# uino-328th.net
KiCad netlist of a schematic drawn in EAGLE
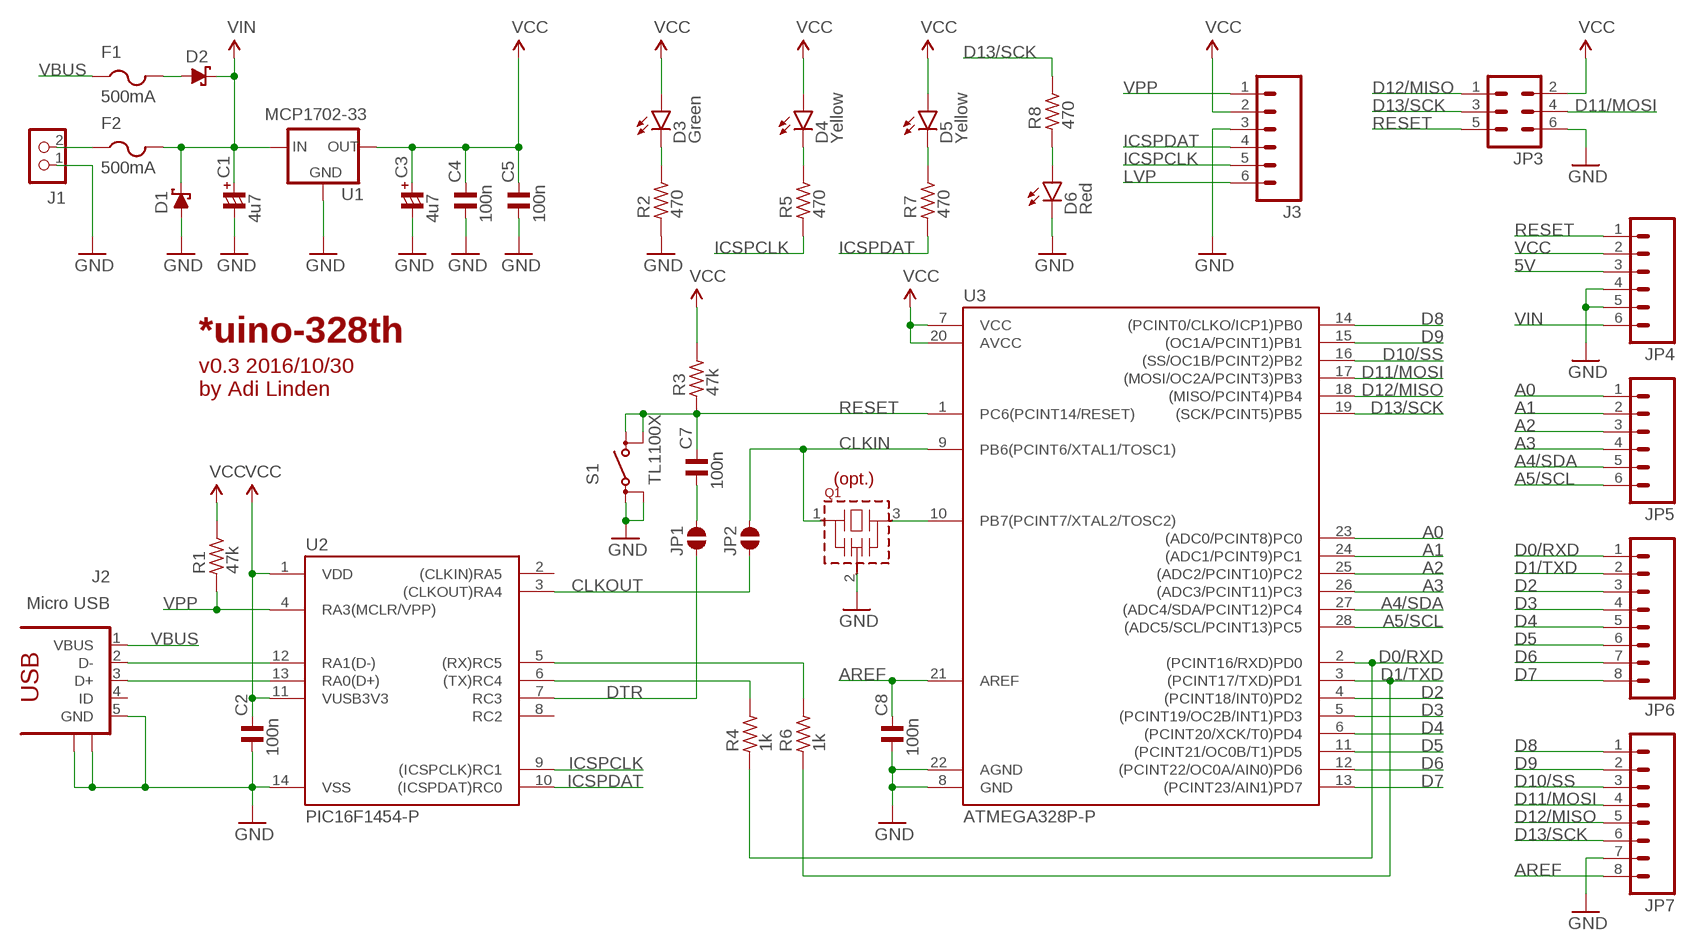
[diagram p0: schematic, sheet 1]

(export (version "E")
  (design (tool "Eeschema 10.0.6"))
  (components
    (comp (ref "C1")
      (value "4u7")
      (footprint "eagle-import:CTT-025-040")
      (libsource (lib "eagle-import") (part "CP_TT025-040"))
    )
    (comp (ref "C2")
      (value "100n")
      (footprint "eagle-import:C025-040X018")
      (libsource (lib "eagle-import") (part "C_C025-040X018"))
    )
    (comp (ref "C3")
      (value "4u7")
      (footprint "eagle-import:CTT-025-040")
      (libsource (lib "eagle-import") (part "CP_TT025-040"))
    )
    (comp (ref "C4")
      (value "100n")
      (footprint "eagle-import:C025-040X018")
      (libsource (lib "eagle-import") (part "C_C025-040X018"))
    )
    (comp (ref "C5")
      (value "100n")
      (footprint "eagle-import:C025-040X018")
      (libsource (lib "eagle-import") (part "C_C025-040X018"))
    )
    (comp (ref "C7")
      (value "100n")
      (footprint "eagle-import:C025-040X018")
      (libsource (lib "eagle-import") (part "C_C025-040X018"))
    )
    (comp (ref "C8")
      (value "100n")
      (footprint "eagle-import:C025-040X018")
      (libsource (lib "eagle-import") (part "C_C025-040X018"))
    )
    (comp (ref "D1")
      (value "SCHOTTKY-DIODEDO35-7")
      (footprint "eagle-import:DO35-7")
      (libsource (lib "eagle-import") (part "SCHOTTKY-DIODEDO35-7"))
    )
    (comp (ref "D2")
      (value "SCHOTTKY-DIODEDO35-7")
      (footprint "eagle-import:DO35-7")
      (libsource (lib "eagle-import") (part "SCHOTTKY-DIODEDO35-7"))
    )
    (comp (ref "D3")
      (value "Green")
      (footprint "eagle-import:LED3MM")
      (libsource (lib "eagle-import") (part "LED3MM"))
    )
    (comp (ref "D4")
      (value "Yellow")
      (footprint "eagle-import:LED3MM")
      (libsource (lib "eagle-import") (part "LED3MM"))
    )
    (comp (ref "D5")
      (value "Yellow")
      (footprint "eagle-import:LED3MM")
      (libsource (lib "eagle-import") (part "LED3MM"))
    )
    (comp (ref "D6")
      (value "Red")
      (footprint "eagle-import:LED3MM")
      (libsource (lib "eagle-import") (part "LED3MM"))
    )
    (comp (ref "F1")
      (value "500mA")
      (footprint "eagle-import:PTC")
      (libsource (lib "eagle-import") (part "FUSE_PTC-TH"))
    )
    (comp (ref "F2")
      (value "500mA")
      (footprint "eagle-import:PTC")
      (libsource (lib "eagle-import") (part "FUSE_PTC-TH"))
    )
    (comp (ref "J1")
      (value "CON_TERMINAL_BLOCK_02-5MM")
      (footprint "eagle-import:TERMINAL_BLOCK_2P_5")
      (libsource (lib "eagle-import") (part "CON_TERMINAL_BLOCK_02-5MM"))
    )
    (comp (ref "J2")
      (value "Micro USB")
      (footprint "eagle-import:ZX62D-AB-5P8")
      (libsource (lib "eagle-import") (part "USB_MICRO_B_2.0-TH"))
    )
    (comp (ref "J3")
      (value "M06LOCK")
      (footprint "eagle-import:1X06_LOCK")
      (libsource (lib "eagle-import") (part "SparkFun-Connectors_M06LOCK"))
    )
    (comp (ref "JP1")
      (value "SJ-035")
      (footprint "eagle-import:SJ-035")
      (libsource (lib "eagle-import") (part "SJ-035"))
    )
    (comp (ref "JP2")
      (value "SJ-035")
      (footprint "eagle-import:SJ-035")
      (libsource (lib "eagle-import") (part "SJ-035"))
    )
    (comp (ref "JP3")
      (value "M03X2")
      (footprint "eagle-import:2X03")
      (libsource (lib "eagle-import") (part "M03X2"))
    )
    (comp (ref "JP4")
      (value "M06SIP")
      (footprint "eagle-import:1X06")
      (libsource (lib "eagle-import") (part "M06SIP"))
    )
    (comp (ref "JP5")
      (value "M06SIP")
      (footprint "eagle-import:1X06")
      (libsource (lib "eagle-import") (part "M06SIP"))
    )
    (comp (ref "JP6")
      (value "M081X08")
      (footprint "eagle-import:1X08")
      (libsource (lib "eagle-import") (part "M081X08"))
    )
    (comp (ref "JP7")
      (value "M081X08")
      (footprint "eagle-import:1X08")
      (libsource (lib "eagle-import") (part "M081X08"))
    )
    (comp (ref "Q1")
      (value "CSTLS_X")
      (footprint "eagle-import:CSTLS_X")
      (libsource (lib "eagle-import") (part "CSTLS_X"))
    )
    (comp (ref "R1")
      (value "47k")
      (footprint "eagle-import:0207_7")
      (libsource (lib "eagle-import") (part "R_X0207/7"))
    )
    (comp (ref "R2")
      (value "470")
      (footprint "eagle-import:0207_7")
      (libsource (lib "eagle-import") (part "R_X0207/7"))
    )
    (comp (ref "R3")
      (value "47k")
      (footprint "eagle-import:0207_7")
      (libsource (lib "eagle-import") (part "R_X0207/7"))
    )
    (comp (ref "R4")
      (value "1k")
      (footprint "eagle-import:0207_10")
      (libsource (lib "eagle-import") (part "R_X0207/10"))
    )
    (comp (ref "R5")
      (value "470")
      (footprint "eagle-import:0207_7")
      (libsource (lib "eagle-import") (part "R_X0207/7"))
    )
    (comp (ref "R6")
      (value "1k")
      (footprint "eagle-import:0207_10")
      (libsource (lib "eagle-import") (part "R_X0207/10"))
    )
    (comp (ref "R7")
      (value "470")
      (footprint "eagle-import:0207_7")
      (libsource (lib "eagle-import") (part "R_X0207/7"))
    )
    (comp (ref "R8")
      (value "470")
      (footprint "eagle-import:0207_10")
      (libsource (lib "eagle-import") (part "R_X0207/10"))
    )
    (comp (ref "S1")
      (value "TL1100X")
      (footprint "eagle-import:TL1100X")
      (libsource (lib "eagle-import") (part "TL1100X"))
    )
    (comp (ref "U1")
      (value "MCP1702-33")
      (footprint "eagle-import:TO-92")
      (libsource (lib "eagle-import") (part "V_REG_MCP170X"))
    )
    (comp (ref "U2")
      (value "PIC16F1454-P")
      (footprint "eagle-import:DIL14")
      (libsource (lib "eagle-import") (part "PIC16F1454-P"))
    )
    (comp (ref "U3")
      (value "ATMEGA328P-P")
      (footprint "eagle-import:DIL28-3")
      (libsource (lib "eagle-import") (part "ATMEGA328P-P"))
    )
  )
  (nets
    (net (code "1") (name "/5V") (class "Default")
      (node (ref "JP4") (pin "3") (pinfunction "3_3") (pintype "passive"))
    )
    (net (code "2") (name "/A0") (class "Default")
      (node (ref "JP5") (pin "1") (pinfunction "1_1") (pintype "passive"))
      (node (ref "U3") (pin "23") (pinfunction "(ADC0/PCINT8)PC0_23") (pintype "bidirectional"))
    )
    (net (code "3") (name "/A1") (class "Default")
      (node (ref "JP5") (pin "2") (pinfunction "2_2") (pintype "passive"))
      (node (ref "U3") (pin "24") (pinfunction "(ADC1/PCINT9)PC1_24") (pintype "bidirectional"))
    )
    (net (code "4") (name "/A2") (class "Default")
      (node (ref "JP5") (pin "3") (pinfunction "3_3") (pintype "passive"))
      (node (ref "U3") (pin "25") (pinfunction "(ADC2/PCINT10)PC2_25") (pintype "bidirectional"))
    )
    (net (code "5") (name "/A3") (class "Default")
      (node (ref "JP5") (pin "4") (pinfunction "4_4") (pintype "passive"))
      (node (ref "U3") (pin "26") (pinfunction "(ADC3/PCINT11)PC3_26") (pintype "bidirectional"))
    )
    (net (code "6") (name "/A4{slash}SDA") (class "Default")
      (node (ref "JP5") (pin "5") (pinfunction "5_5") (pintype "passive"))
      (node (ref "U3") (pin "27") (pinfunction "(ADC4/SDA/PCINT12)PC4_27") (pintype "bidirectional"))
    )
    (net (code "7") (name "/A5{slash}SCL") (class "Default")
      (node (ref "JP5") (pin "6") (pinfunction "6_6") (pintype "passive"))
      (node (ref "U3") (pin "28") (pinfunction "(ADC5/SCL/PCINT13)PC5_28") (pintype "bidirectional"))
    )
    (net (code "8") (name "/AREF") (class "Default")
      (node (ref "C8") (pin "2") (pinfunction "2_2") (pintype "passive"))
      (node (ref "JP7") (pin "8") (pinfunction "8_8") (pintype "passive"))
      (node (ref "U3") (pin "21") (pinfunction "AREF_21") (pintype "input"))
    )
    (net (code "9") (name "/CLKIN") (class "Default")
      (node (ref "JP2") (pin "2") (pinfunction "2_2") (pintype "passive"))
      (node (ref "Q1") (pin "1") (pinfunction "1_1") (pintype "output"))
      (node (ref "U3") (pin "9") (pinfunction "PB6(PCINT6/XTAL1/TOSC1)_9") (pintype "bidirectional"))
    )
    (net (code "10") (name "/CLKOUT") (class "Default")
      (node (ref "JP2") (pin "1") (pinfunction "1_1") (pintype "passive"))
      (node (ref "U2") (pin "3") (pinfunction "(CLKOUT)RA4_3") (pintype "bidirectional"))
    )
    (net (code "11") (name "/D0{slash}RXD") (class "Default")
      (node (ref "JP6") (pin "1") (pinfunction "1_1") (pintype "passive"))
      (node (ref "R4") (pin "1") (pinfunction "1_1") (pintype "passive"))
      (node (ref "U3") (pin "2") (pinfunction "(PCINT16/RXD)PD0_2") (pintype "bidirectional"))
    )
    (net (code "12") (name "/D1{slash}TXD") (class "Default")
      (node (ref "JP6") (pin "2") (pinfunction "2_2") (pintype "passive"))
      (node (ref "R6") (pin "1") (pinfunction "1_1") (pintype "passive"))
      (node (ref "U3") (pin "3") (pinfunction "(PCINT17/TXD)PD1_3") (pintype "bidirectional"))
    )
    (net (code "13") (name "/D2") (class "Default")
      (node (ref "JP6") (pin "3") (pinfunction "3_3") (pintype "passive"))
      (node (ref "U3") (pin "4") (pinfunction "(PCINT18/INT0)PD2_4") (pintype "bidirectional"))
    )
    (net (code "14") (name "/D3") (class "Default")
      (node (ref "JP6") (pin "4") (pinfunction "4_4") (pintype "passive"))
      (node (ref "U3") (pin "5") (pinfunction "(PCINT19/OC2B/INT1)PD3_5") (pintype "bidirectional"))
    )
    (net (code "15") (name "/D4") (class "Default")
      (node (ref "JP6") (pin "5") (pinfunction "5_5") (pintype "passive"))
      (node (ref "U3") (pin "6") (pinfunction "(PCINT20/XCK/T0)PD4_6") (pintype "bidirectional"))
    )
    (net (code "16") (name "/D5") (class "Default")
      (node (ref "JP6") (pin "6") (pinfunction "6_6") (pintype "passive"))
      (node (ref "U3") (pin "11") (pinfunction "(PCINT21/OC0B/T1)PD5_11") (pintype "bidirectional"))
    )
    (net (code "17") (name "/D6") (class "Default")
      (node (ref "JP6") (pin "7") (pinfunction "7_7") (pintype "passive"))
      (node (ref "U3") (pin "12") (pinfunction "(PCINT22/OC0A/AIN0)PD6_12") (pintype "bidirectional"))
    )
    (net (code "18") (name "/D7") (class "Default")
      (node (ref "JP6") (pin "8") (pinfunction "8_8") (pintype "passive"))
      (node (ref "U3") (pin "13") (pinfunction "(PCINT23/AIN1)PD7_13") (pintype "bidirectional"))
    )
    (net (code "19") (name "/D8") (class "Default")
      (node (ref "JP7") (pin "1") (pinfunction "1_1") (pintype "passive"))
      (node (ref "U3") (pin "14") (pinfunction "(PCINT0/CLKO/ICP1)PB0_14") (pintype "bidirectional"))
    )
    (net (code "20") (name "/D9") (class "Default")
      (node (ref "JP7") (pin "2") (pinfunction "2_2") (pintype "passive"))
      (node (ref "U3") (pin "15") (pinfunction "(OC1A/PCINT1)PB1_15") (pintype "bidirectional"))
    )
    (net (code "21") (name "/D10{slash}SS") (class "Default")
      (node (ref "JP7") (pin "3") (pinfunction "3_3") (pintype "passive"))
      (node (ref "U3") (pin "16") (pinfunction "(SS/OC1B/PCINT2)PB2_16") (pintype "bidirectional"))
    )
    (net (code "22") (name "/D11{slash}MOSI") (class "Default")
      (node (ref "JP3") (pin "4") (pinfunction "4_4") (pintype "passive"))
      (node (ref "JP7") (pin "4") (pinfunction "4_4") (pintype "passive"))
      (node (ref "U3") (pin "17") (pinfunction "(MOSI/OC2A/PCINT3)PB3_17") (pintype "bidirectional"))
    )
    (net (code "23") (name "/D12{slash}MISO") (class "Default")
      (node (ref "JP3") (pin "1") (pinfunction "1_1") (pintype "passive"))
      (node (ref "JP7") (pin "5") (pinfunction "5_5") (pintype "passive"))
      (node (ref "U3") (pin "18") (pinfunction "(MISO/PCINT4)PB4_18") (pintype "bidirectional"))
    )
    (net (code "24") (name "/D13{slash}SCK") (class "Default")
      (node (ref "JP3") (pin "3") (pinfunction "3_3") (pintype "passive"))
      (node (ref "JP7") (pin "6") (pinfunction "6_6") (pintype "passive"))
      (node (ref "R8") (pin "2") (pinfunction "2_2") (pintype "passive"))
      (node (ref "U3") (pin "19") (pinfunction "(SCK/PCINT5)PB5_19") (pintype "bidirectional"))
    )
    (net (code "25") (name "/DTR") (class "Default")
      (node (ref "JP1") (pin "1") (pinfunction "1_1") (pintype "passive"))
      (node (ref "U2") (pin "7") (pinfunction "RC3_7") (pintype "bidirectional"))
    )
    (net (code "26") (name "/ICSPCLK") (class "Default")
      (node (ref "J3") (pin "5") (pinfunction "5_5") (pintype "passive"))
      (node (ref "R5") (pin "1") (pinfunction "1_1") (pintype "passive"))
      (node (ref "U2") (pin "9") (pinfunction "(ICSPCLK)RC1_9") (pintype "bidirectional"))
    )
    (net (code "27") (name "/ICSPDAT") (class "Default")
      (node (ref "J3") (pin "4") (pinfunction "4_4") (pintype "passive"))
      (node (ref "R7") (pin "1") (pinfunction "1_1") (pintype "passive"))
      (node (ref "U2") (pin "10") (pinfunction "(ICSPDAT)RC0_10") (pintype "bidirectional"))
    )
    (net (code "28") (name "/LVP") (class "Default")
      (node (ref "J3") (pin "6") (pinfunction "6_6") (pintype "passive"))
    )
    (net (code "29") (name "/RESET") (class "Default")
      (node (ref "C7") (pin "2") (pinfunction "2_2") (pintype "passive"))
      (node (ref "JP3") (pin "5") (pinfunction "5_5") (pintype "passive"))
      (node (ref "JP4") (pin "1") (pinfunction "1_1") (pintype "passive"))
      (node (ref "R3") (pin "1") (pinfunction "1_1") (pintype "passive"))
      (node (ref "S1") (pin "3") (pinfunction "S_3") (pintype "passive"))
      (node (ref "S1") (pin "4") (pinfunction "S1_4") (pintype "passive"))
      (node (ref "U3") (pin "1") (pinfunction "PC6(PCINT14/RESET)_1") (pintype "bidirectional"))
    )
    (net (code "30") (name "/VBUS") (class "Default")
      (node (ref "F1") (pin "P$1") (pinfunction "1_P$1") (pintype "passive"))
      (node (ref "J2") (pin "1") (pinfunction "VBUS_1") (pintype "passive"))
    )
    (net (code "31") (name "/VPP") (class "Default")
      (node (ref "J3") (pin "1") (pinfunction "1_1") (pintype "passive"))
      (node (ref "R1") (pin "1") (pinfunction "1_1") (pintype "passive"))
      (node (ref "U2") (pin "4") (pinfunction "RA3(MCLR/VPP)_4") (pintype "bidirectional"))
    )
    (net (code "32") (name "GND") (class "Default")
      (node (ref "C1") (pin "-") (pinfunction "-_-") (pintype "passive"))
      (node (ref "C2") (pin "1") (pinfunction "1_1") (pintype "passive"))
      (node (ref "C3") (pin "-") (pinfunction "-_-") (pintype "passive"))
      (node (ref "C4") (pin "1") (pinfunction "1_1") (pintype "passive"))
      (node (ref "C5") (pin "1") (pinfunction "1_1") (pintype "passive"))
      (node (ref "C8") (pin "1") (pinfunction "1_1") (pintype "passive"))
      (node (ref "D1") (pin "A") (pinfunction "A_A") (pintype "passive"))
      (node (ref "D6") (pin "K") (pinfunction "C_K") (pintype "passive"))
      (node (ref "J1") (pin "1") (pinfunction "1_1") (pintype "passive"))
      (node (ref "J2") (pin "5") (pinfunction "GND_5") (pintype "passive"))
      (node (ref "J2") (pin "S1") (pinfunction "S1_S1") (pintype "passive"))
      (node (ref "J2") (pin "S2") (pinfunction "S2_S2") (pintype "passive"))
      (node (ref "J3") (pin "3") (pinfunction "3_3") (pintype "passive"))
      (node (ref "JP3") (pin "6") (pinfunction "6_6") (pintype "passive"))
      (node (ref "JP4") (pin "4") (pinfunction "4_4") (pintype "passive"))
      (node (ref "JP4") (pin "5") (pinfunction "5_5") (pintype "passive"))
      (node (ref "JP7") (pin "7") (pinfunction "7_7") (pintype "passive"))
      (node (ref "Q1") (pin "2") (pinfunction "VSS_2") (pintype "power_in"))
      (node (ref "R2") (pin "1") (pinfunction "1_1") (pintype "passive"))
      (node (ref "S1") (pin "1") (pinfunction "P_1") (pintype "passive"))
      (node (ref "S1") (pin "2") (pinfunction "P1_2") (pintype "passive"))
      (node (ref "U1") (pin "1") (pinfunction "GND_1") (pintype "input"))
      (node (ref "U2") (pin "14") (pinfunction "VSS_14") (pintype "power_in"))
      (node (ref "U3") (pin "22") (pinfunction "AGND_22") (pintype "power_in"))
      (node (ref "U3") (pin "8") (pinfunction "GND_8") (pintype "power_in"))
    )
    (net (code "33") (name "Net-(C7-Pad1)") (class "Default")
      (node (ref "C7") (pin "1") (pinfunction "1_1") (pintype "passive"))
      (node (ref "JP1") (pin "2") (pinfunction "2_2") (pintype "passive"))
    )
    (net (code "34") (name "Net-(D3-C)") (class "Default")
      (node (ref "D3") (pin "K") (pinfunction "C_K") (pintype "passive"))
      (node (ref "R2") (pin "2") (pinfunction "2_2") (pintype "passive"))
    )
    (net (code "35") (name "Net-(D4-C)") (class "Default")
      (node (ref "D4") (pin "K") (pinfunction "C_K") (pintype "passive"))
      (node (ref "R5") (pin "2") (pinfunction "2_2") (pintype "passive"))
    )
    (net (code "36") (name "Net-(D5-C)") (class "Default")
      (node (ref "D5") (pin "K") (pinfunction "C_K") (pintype "passive"))
      (node (ref "R7") (pin "2") (pinfunction "2_2") (pintype "passive"))
    )
    (net (code "37") (name "Net-(D6-PadA)") (class "Default")
      (node (ref "D6") (pin "A") (pinfunction "A_A") (pintype "passive"))
      (node (ref "R8") (pin "1") (pinfunction "1_1") (pintype "passive"))
    )
    (net (code "38") (name "Net-(F1-2)") (class "Default")
      (node (ref "D2") (pin "A") (pinfunction "A_A") (pintype "passive"))
      (node (ref "F1") (pin "P$2") (pinfunction "2_P$2") (pintype "passive"))
    )
    (net (code "39") (name "Net-(F2-1)") (class "Default")
      (node (ref "F2") (pin "P$1") (pinfunction "1_P$1") (pintype "passive"))
      (node (ref "J1") (pin "2") (pinfunction "2_2") (pintype "passive"))
    )
    (net (code "40") (name "Net-(J2-D+)") (class "Default")
      (node (ref "J2") (pin "3") (pinfunction "D+_3") (pintype "passive"))
      (node (ref "U2") (pin "13") (pinfunction "RA0(D+)_13") (pintype "bidirectional"))
    )
    (net (code "41") (name "Net-(J2-D-)") (class "Default")
      (node (ref "J2") (pin "2") (pinfunction "D-_2") (pintype "passive"))
      (node (ref "U2") (pin "12") (pinfunction "RA1(D-)_12") (pintype "bidirectional"))
    )
    (net (code "42") (name "Net-(U2-(RX)RC5)") (class "Default")
      (node (ref "R6") (pin "2") (pinfunction "2_2") (pintype "passive"))
      (node (ref "U2") (pin "5") (pinfunction "(RX)RC5_5") (pintype "bidirectional"))
    )
    (net (code "43") (name "Net-(U2-(TX)RC4)") (class "Default")
      (node (ref "R4") (pin "2") (pinfunction "2_2") (pintype "passive"))
      (node (ref "U2") (pin "6") (pinfunction "(TX)RC4_6") (pintype "bidirectional"))
    )
    (net (code "44") (name "Net-(U3-PB7(PCINT7{slash}XTAL2{slash}TOSC2))") (class "Default")
      (node (ref "Q1") (pin "3") (pinfunction "3_3") (pintype "input"))
      (node (ref "U3") (pin "10") (pinfunction "PB7(PCINT7/XTAL2/TOSC2)_10") (pintype "bidirectional"))
    )
    (net (code "45") (name "VCC") (class "Default")
      (node (ref "C2") (pin "2") (pinfunction "2_2") (pintype "passive"))
      (node (ref "C3") (pin "+") (pinfunction "+_+") (pintype "passive"))
      (node (ref "C4") (pin "2") (pinfunction "2_2") (pintype "passive"))
      (node (ref "C5") (pin "2") (pinfunction "2_2") (pintype "passive"))
      (node (ref "D3") (pin "A") (pinfunction "A_A") (pintype "passive"))
      (node (ref "D4") (pin "A") (pinfunction "A_A") (pintype "passive"))
      (node (ref "D5") (pin "A") (pinfunction "A_A") (pintype "passive"))
      (node (ref "J3") (pin "2") (pinfunction "2_2") (pintype "passive"))
      (node (ref "JP3") (pin "2") (pinfunction "2_2") (pintype "passive"))
      (node (ref "JP4") (pin "2") (pinfunction "2_2") (pintype "passive"))
      (node (ref "R1") (pin "2") (pinfunction "2_2") (pintype "passive"))
      (node (ref "R3") (pin "2") (pinfunction "2_2") (pintype "passive"))
      (node (ref "U1") (pin "3") (pinfunction "OUT_3") (pintype "power_in"))
      (node (ref "U2") (pin "1") (pinfunction "VDD_1") (pintype "power_in"))
      (node (ref "U2") (pin "11") (pinfunction "VUSB3V3_11") (pintype "power_in"))
      (node (ref "U3") (pin "20") (pinfunction "AVCC_20") (pintype "power_in"))
      (node (ref "U3") (pin "7") (pinfunction "VCC_7") (pintype "power_in"))
    )
    (net (code "46") (name "VIN") (class "Default")
      (node (ref "C1") (pin "+") (pinfunction "+_+") (pintype "passive"))
      (node (ref "D1") (pin "C") (pinfunction "C_C") (pintype "passive"))
      (node (ref "D2") (pin "C") (pinfunction "C_C") (pintype "passive"))
      (node (ref "F2") (pin "P$2") (pinfunction "2_P$2") (pintype "passive"))
      (node (ref "JP4") (pin "6") (pinfunction "6_6") (pintype "passive"))
      (node (ref "U1") (pin "2") (pinfunction "IN_2") (pintype "input"))
    )
    (net (code "47") (name "unconnected-(J2-ID-Pad4)") (class "Default")
      (node (ref "J2") (pin "4") (pinfunction "ID_4") (pintype "passive"))
    )
    (net (code "48") (name "unconnected-(U2-(CLKIN)RA5-Pad2)") (class "Default")
      (node (ref "U2") (pin "2") (pinfunction "(CLKIN)RA5_2") (pintype "bidirectional"))
    )
    (net (code "49") (name "unconnected-(U2-RC2-Pad8)") (class "Default")
      (node (ref "U2") (pin "8") (pinfunction "RC2_8") (pintype "bidirectional"))
    )
  )
)
